# Steering_Wheel_Interface_Analog_Inputs.net
KiCad netlist of a schematic drawn in Altium Designer
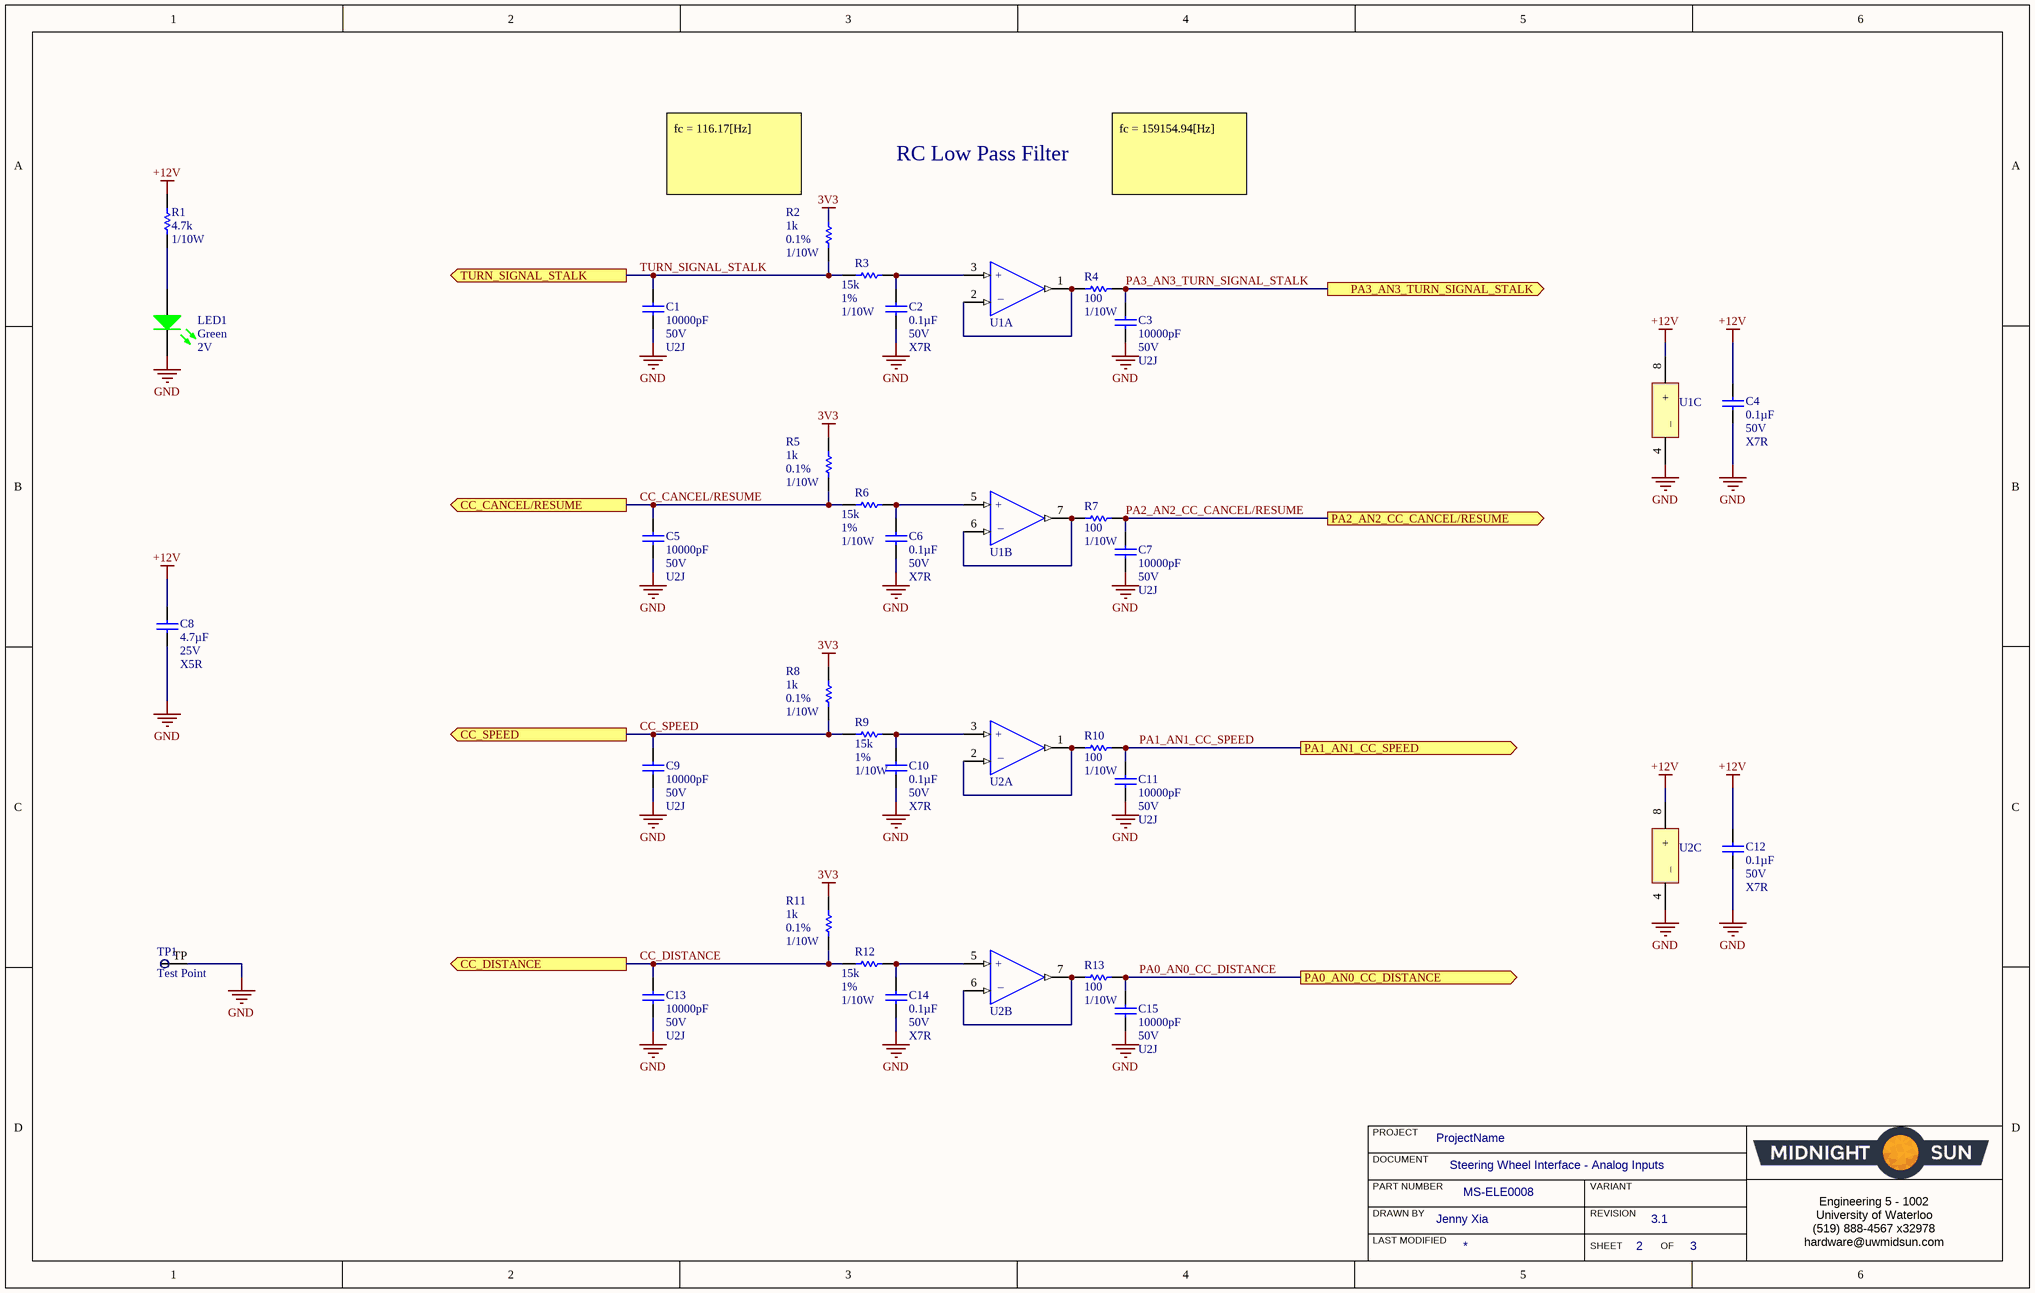
[diagram p0: Steering Wheel Interface Analog Inputs.SchDoc]

(export (version "E")
  (design (tool "Eeschema 10.0.6"))
  (components
    (comp (ref "C1")
      (value "CAP CER 10nF 50V 5% X7R 0603")
      (footprint "CAP, 0603")
      (description "10000pF ±5% 50V Ceramic Capacitor U2J 0603 (1608 Metric)")
      (fields
        (field (name "TOLERANCE") "±5%")
        (field (name "CAPACITANCE") "10000pF")
        (field (name "VOLTAGE") "50V")
        (field (name "TEMPERATURE COEFFICIENT") "U2J")
      )
      (libsource (lib "Schematic Diagrams") (part "CAP CER 10nF 50V 5% X7R 0603"))
    )
    (comp (ref "C2")
      (value "CAP CER 0.1UF 50V 10% X7R 0603")
      (footprint "CAP, 0603")
      (description "0.10µF ±10% 50V Ceramic Capacitor X7R 0603 (1608 Metric)")
      (fields
        (field (name "TOLERANCE") "±10%")
        (field (name "CAPACITANCE") "0.1µF")
        (field (name "VOLTAGE") "50V")
        (field (name "TEMPERATURE COEFFICIENT") "X7R")
      )
      (libsource (lib "Schematic Diagrams") (part "CAP CER 0.1UF 50V 10% X7R 0603"))
    )
    (comp (ref "C3")
      (value "CAP CER 10nF 50V 5% X7R 0603")
      (footprint "CAP, 0603")
      (description "10000pF ±5% 50V Ceramic Capacitor U2J 0603 (1608 Metric)")
      (fields
        (field (name "TOLERANCE") "±5%")
        (field (name "CAPACITANCE") "10000pF")
        (field (name "VOLTAGE") "50V")
        (field (name "TEMPERATURE COEFFICIENT") "U2J")
      )
      (libsource (lib "Schematic Diagrams") (part "CAP CER 10nF 50V 5% X7R 0603"))
    )
    (comp (ref "C4")
      (value "CAP CER 0.1UF 50V 10% X7R 0603")
      (footprint "CAP, 0603")
      (description "0.10µF ±10% 50V Ceramic Capacitor X7R 0603 (1608 Metric)")
      (fields
        (field (name "TOLERANCE") "±10%")
        (field (name "CAPACITANCE") "0.1µF")
        (field (name "VOLTAGE") "50V")
        (field (name "TEMPERATURE COEFFICIENT") "X7R")
      )
      (libsource (lib "Schematic Diagrams") (part "CAP CER 0.1UF 50V 10% X7R 0603"))
    )
    (comp (ref "C5")
      (value "CAP CER 10nF 50V 5% X7R 0603")
      (footprint "CAP, 0603")
      (description "10000pF ±5% 50V Ceramic Capacitor U2J 0603 (1608 Metric)")
      (fields
        (field (name "TOLERANCE") "±5%")
        (field (name "CAPACITANCE") "10000pF")
        (field (name "VOLTAGE") "50V")
        (field (name "TEMPERATURE COEFFICIENT") "U2J")
      )
      (libsource (lib "Schematic Diagrams") (part "CAP CER 10nF 50V 5% X7R 0603"))
    )
    (comp (ref "C6")
      (value "CAP CER 0.1UF 50V 10% X7R 0603")
      (footprint "CAP, 0603")
      (description "0.10µF ±10% 50V Ceramic Capacitor X7R 0603 (1608 Metric)")
      (fields
        (field (name "TOLERANCE") "±10%")
        (field (name "CAPACITANCE") "0.1µF")
        (field (name "VOLTAGE") "50V")
        (field (name "TEMPERATURE COEFFICIENT") "X7R")
      )
      (libsource (lib "Schematic Diagrams") (part "CAP CER 0.1UF 50V 10% X7R 0603"))
    )
    (comp (ref "C7")
      (value "CAP CER 10nF 50V 5% X7R 0603")
      (footprint "CAP, 0603")
      (description "10000pF ±5% 50V Ceramic Capacitor U2J 0603 (1608 Metric)")
      (fields
        (field (name "TOLERANCE") "±5%")
        (field (name "CAPACITANCE") "10000pF")
        (field (name "VOLTAGE") "50V")
        (field (name "TEMPERATURE COEFFICIENT") "U2J")
      )
      (libsource (lib "Schematic Diagrams") (part "CAP CER 10nF 50V 5% X7R 0603"))
    )
    (comp (ref "C8")
      (value "CAP CER 4.7UF 25V 10% X5R 0603")
      (footprint "CAP, 0603")
      (description "4.7µF ±10% 25V Ceramic Capacitor X5R 0603 (1608 Metric)")
      (fields
        (field (name "TOLERANCE") "±10%")
        (field (name "CAPACITANCE") "4.7µF")
        (field (name "VOLTAGE") "25V")
        (field (name "TEMPERATURE COEFFICIENT") "X5R")
      )
      (libsource (lib "Schematic Diagrams") (part "CAP CER 4.7UF 25V 10% X5R 0603"))
    )
    (comp (ref "C9")
      (value "CAP CER 10nF 50V 5% X7R 0603")
      (footprint "CAP, 0603")
      (description "10000pF ±5% 50V Ceramic Capacitor U2J 0603 (1608 Metric)")
      (fields
        (field (name "TOLERANCE") "±5%")
        (field (name "CAPACITANCE") "10000pF")
        (field (name "VOLTAGE") "50V")
        (field (name "TEMPERATURE COEFFICIENT") "U2J")
      )
      (libsource (lib "Schematic Diagrams") (part "CAP CER 10nF 50V 5% X7R 0603"))
    )
    (comp (ref "C10")
      (value "CAP CER 0.1UF 50V 10% X7R 0603")
      (footprint "CAP, 0603")
      (description "0.10µF ±10% 50V Ceramic Capacitor X7R 0603 (1608 Metric)")
      (fields
        (field (name "TOLERANCE") "±10%")
        (field (name "CAPACITANCE") "0.1µF")
        (field (name "VOLTAGE") "50V")
        (field (name "TEMPERATURE COEFFICIENT") "X7R")
      )
      (libsource (lib "Schematic Diagrams") (part "CAP CER 0.1UF 50V 10% X7R 0603"))
    )
    (comp (ref "C11")
      (value "CAP CER 10nF 50V 5% X7R 0603")
      (footprint "CAP, 0603")
      (description "10000pF ±5% 50V Ceramic Capacitor U2J 0603 (1608 Metric)")
      (fields
        (field (name "TOLERANCE") "±5%")
        (field (name "CAPACITANCE") "10000pF")
        (field (name "VOLTAGE") "50V")
        (field (name "TEMPERATURE COEFFICIENT") "U2J")
      )
      (libsource (lib "Schematic Diagrams") (part "CAP CER 10nF 50V 5% X7R 0603"))
    )
    (comp (ref "C12")
      (value "CAP CER 0.1UF 50V 10% X7R 0603")
      (footprint "CAP, 0603")
      (description "0.10µF ±10% 50V Ceramic Capacitor X7R 0603 (1608 Metric)")
      (fields
        (field (name "TOLERANCE") "±10%")
        (field (name "CAPACITANCE") "0.1µF")
        (field (name "VOLTAGE") "50V")
        (field (name "TEMPERATURE COEFFICIENT") "X7R")
      )
      (libsource (lib "Schematic Diagrams") (part "CAP CER 0.1UF 50V 10% X7R 0603"))
    )
    (comp (ref "C13")
      (value "CAP CER 10nF 50V 5% X7R 0603")
      (footprint "CAP, 0603")
      (description "10000pF ±5% 50V Ceramic Capacitor U2J 0603 (1608 Metric)")
      (fields
        (field (name "TOLERANCE") "±5%")
        (field (name "CAPACITANCE") "10000pF")
        (field (name "VOLTAGE") "50V")
        (field (name "TEMPERATURE COEFFICIENT") "U2J")
      )
      (libsource (lib "Schematic Diagrams") (part "CAP CER 10nF 50V 5% X7R 0603"))
    )
    (comp (ref "C14")
      (value "CAP CER 0.1UF 50V 10% X7R 0603")
      (footprint "CAP, 0603")
      (description "0.10µF ±10% 50V Ceramic Capacitor X7R 0603 (1608 Metric)")
      (fields
        (field (name "TOLERANCE") "±10%")
        (field (name "CAPACITANCE") "0.1µF")
        (field (name "VOLTAGE") "50V")
        (field (name "TEMPERATURE COEFFICIENT") "X7R")
      )
      (libsource (lib "Schematic Diagrams") (part "CAP CER 0.1UF 50V 10% X7R 0603"))
    )
    (comp (ref "C15")
      (value "CAP CER 10nF 50V 5% X7R 0603")
      (footprint "CAP, 0603")
      (description "10000pF ±5% 50V Ceramic Capacitor U2J 0603 (1608 Metric)")
      (fields
        (field (name "TOLERANCE") "±5%")
        (field (name "CAPACITANCE") "10000pF")
        (field (name "VOLTAGE") "50V")
        (field (name "TEMPERATURE COEFFICIENT") "U2J")
      )
      (libsource (lib "Schematic Diagrams") (part "CAP CER 10nF 50V 5% X7R 0603"))
    )
    (comp (ref "LED1")
      (value "LED GREEN CLEAR 2V 0603")
      (footprint "LED_0603")
      (description "Green 572nm LED Indication - Discrete 2V 0603 (1608 Metric)")
      (fields
        (field (name "MANUFACTURER") "Wurth Electronics Inc.")
        (field (name "MANUFACTURER PART NUMBER") "150060VS75000")
        (field (name "COLOR") "Green")
        (field (name "VOLTAGE - FORWARD (VF) (TYP)") "2V")
      )
      (libsource (lib "Schematic Diagrams") (part "LED GREEN CLEAR 2V 0603"))
    )
    (comp (ref "R1")
      (value "RES 4.7K OHM 1% 1/10W 0603")
      (footprint "RES, 0603")
      (description "4.7k Ohm ±1% 0.1W, 1/10W Chip Resistor 0603 (1608 Metric) Moisture Resistant Thick Film")
      (fields
        (field (name "TOLERANCE") "±1%")
        (field (name "RESISTANCE (OHMS)") "4.7k")
        (field (name "POWER (WATTS)") "1/10W")
      )
      (libsource (lib "Schematic Diagrams") (part "RES 4.7K OHM 1% 1/10W 0603"))
    )
    (comp (ref "R2")
      (value "RES SMD 1K OHM 0.1% 1/10W 0603")
      (footprint "RES, 0603")
      (description "1 kOhms ±0.1% 0.1W, 1/10W Chip Resistor 0603 (1608 Metric) Automotive AEC-Q200 Thin Film")
      (fields
        (field (name "MANUFACTURER") "Panasonic")
        (field (name "MANUFACTURER PART NUMBER") "ERA3AEB102V")
        (field (name "RESISTANCE") "1k")
        (field (name "TOLERANCE") "0.1%")
        (field (name "POWER RATING") "1/10W")
      )
      (libsource (lib "Schematic Diagrams") (part "RES SMD 1K OHM 0.1% 1/10W 0603"))
    )
    (comp (ref "R3")
      (value "RES SMD 15K OHM 1% 1/10W 0603")
      (footprint "RES, 0603")
      (description "15 kOhms ±1% 0.1W, 1/10W Chip Resistor 0603 (1608 Metric) Moisture Resistant Thick Film")
      (fields
        (field (name "RESISTANCE") "15k")
        (field (name "TOLERANCE") "1%")
        (field (name "MAX POWER DISSIPATION") "1/10W")
        (field (name "MANUFACTURER") "Yageo")
        (field (name "MANUFACTURER PART NUMBER") "RC0603FR-0715KL")
      )
      (libsource (lib "Schematic Diagrams") (part "RES SMD 15K OHM 1% 1/10W 0603"))
    )
    (comp (ref "R4")
      (value "RES 100 OHM 1% 1/10W 0603")
      (footprint "RES, 0603")
      (description "100 Ohm ±1% 0.1W, 1/10W Chip Resistor 0603 (1608 Metric) Moisture Resistant Thick Film")
      (fields
        (field (name "TOLERANCE") "±1%")
        (field (name "RESISTANCE") "100")
        (field (name "POWER") "1/10W")
      )
      (libsource (lib "Schematic Diagrams") (part "RES 100 OHM 1% 1/10W 0603"))
    )
    (comp (ref "R5")
      (value "RES SMD 1K OHM 0.1% 1/10W 0603")
      (footprint "RES, 0603")
      (description "1 kOhms ±0.1% 0.1W, 1/10W Chip Resistor 0603 (1608 Metric) Automotive AEC-Q200 Thin Film")
      (fields
        (field (name "MANUFACTURER") "Panasonic")
        (field (name "MANUFACTURER PART NUMBER") "ERA3AEB102V")
        (field (name "RESISTANCE") "1k")
        (field (name "TOLERANCE") "0.1%")
        (field (name "POWER RATING") "1/10W")
      )
      (libsource (lib "Schematic Diagrams") (part "RES SMD 1K OHM 0.1% 1/10W 0603"))
    )
    (comp (ref "R6")
      (value "RES SMD 15K OHM 1% 1/10W 0603")
      (footprint "RES, 0603")
      (description "15 kOhms ±1% 0.1W, 1/10W Chip Resistor 0603 (1608 Metric) Moisture Resistant Thick Film")
      (fields
        (field (name "RESISTANCE") "15k")
        (field (name "TOLERANCE") "1%")
        (field (name "MAX POWER DISSIPATION") "1/10W")
        (field (name "MANUFACTURER") "Yageo")
        (field (name "MANUFACTURER PART NUMBER") "RC0603FR-0715KL")
      )
      (libsource (lib "Schematic Diagrams") (part "RES SMD 15K OHM 1% 1/10W 0603"))
    )
    (comp (ref "R7")
      (value "RES 100 OHM 1% 1/10W 0603")
      (footprint "RES, 0603")
      (description "100 Ohm ±1% 0.1W, 1/10W Chip Resistor 0603 (1608 Metric) Moisture Resistant Thick Film")
      (fields
        (field (name "TOLERANCE") "±1%")
        (field (name "RESISTANCE") "100")
        (field (name "POWER") "1/10W")
      )
      (libsource (lib "Schematic Diagrams") (part "RES 100 OHM 1% 1/10W 0603"))
    )
    (comp (ref "R8")
      (value "RES SMD 1K OHM 0.1% 1/10W 0603")
      (footprint "RES, 0603")
      (description "1 kOhms ±0.1% 0.1W, 1/10W Chip Resistor 0603 (1608 Metric) Automotive AEC-Q200 Thin Film")
      (fields
        (field (name "MANUFACTURER") "Panasonic")
        (field (name "MANUFACTURER PART NUMBER") "ERA3AEB102V")
        (field (name "RESISTANCE") "1k")
        (field (name "TOLERANCE") "0.1%")
        (field (name "POWER RATING") "1/10W")
      )
      (libsource (lib "Schematic Diagrams") (part "RES SMD 1K OHM 0.1% 1/10W 0603"))
    )
    (comp (ref "R9")
      (value "RES SMD 15K OHM 1% 1/10W 0603")
      (footprint "RES, 0603")
      (description "15 kOhms ±1% 0.1W, 1/10W Chip Resistor 0603 (1608 Metric) Moisture Resistant Thick Film")
      (fields
        (field (name "RESISTANCE") "15k")
        (field (name "TOLERANCE") "1%")
        (field (name "MAX POWER DISSIPATION") "1/10W")
        (field (name "MANUFACTURER") "Yageo")
        (field (name "MANUFACTURER PART NUMBER") "RC0603FR-0715KL")
      )
      (libsource (lib "Schematic Diagrams") (part "RES SMD 15K OHM 1% 1/10W 0603"))
    )
    (comp (ref "R10")
      (value "RES 100 OHM 1% 1/10W 0603")
      (footprint "RES, 0603")
      (description "100 Ohm ±1% 0.1W, 1/10W Chip Resistor 0603 (1608 Metric) Moisture Resistant Thick Film")
      (fields
        (field (name "TOLERANCE") "±1%")
        (field (name "RESISTANCE") "100")
        (field (name "POWER") "1/10W")
      )
      (libsource (lib "Schematic Diagrams") (part "RES 100 OHM 1% 1/10W 0603"))
    )
    (comp (ref "R11")
      (value "RES SMD 1K OHM 0.1% 1/10W 0603")
      (footprint "RES, 0603")
      (description "1 kOhms ±0.1% 0.1W, 1/10W Chip Resistor 0603 (1608 Metric) Automotive AEC-Q200 Thin Film")
      (fields
        (field (name "RESISTANCE") "1k")
        (field (name "TOLERANCE") "0.1%")
        (field (name "POWER RATING") "1/10W")
        (field (name "MANUFACTURER") "Panasonic")
        (field (name "MANUFACTURER PART NUMBER") "ERA3AEB102V")
      )
      (libsource (lib "Schematic Diagrams") (part "RES SMD 1K OHM 0.1% 1/10W 0603"))
    )
    (comp (ref "R12")
      (value "RES SMD 15K OHM 1% 1/10W 0603")
      (footprint "RES, 0603")
      (description "15 kOhms ±1% 0.1W, 1/10W Chip Resistor 0603 (1608 Metric) Moisture Resistant Thick Film")
      (fields
        (field (name "RESISTANCE") "15k")
        (field (name "TOLERANCE") "1%")
        (field (name "MAX POWER DISSIPATION") "1/10W")
        (field (name "MANUFACTURER") "Yageo")
        (field (name "MANUFACTURER PART NUMBER") "RC0603FR-0715KL")
      )
      (libsource (lib "Schematic Diagrams") (part "RES SMD 15K OHM 1% 1/10W 0603"))
    )
    (comp (ref "R13")
      (value "RES 100 OHM 1% 1/10W 0603")
      (footprint "RES, 0603")
      (description "100 Ohm ±1% 0.1W, 1/10W Chip Resistor 0603 (1608 Metric) Moisture Resistant Thick Film")
      (fields
        (field (name "TOLERANCE") "±1%")
        (field (name "RESISTANCE") "100")
        (field (name "POWER") "1/10W")
      )
      (libsource (lib "Schematic Diagrams") (part "RES 100 OHM 1% 1/10W 0603"))
    )
    (comp (ref "TP1")
      (value "Test Point")
      (footprint "Test Point")
      (libsource (lib "Schematic Diagrams") (part "Test Point"))
    )
    (comp (ref "U1")
      (value "IC OP AMP DUAL GP RR 10MHZ 8-VSSOP")
      (footprint "IC OP AMP DUAL 8-VSSOP")
      (description "General Purpose Amplifier 2 Circuit Rail-to-Rail 8-VSSOP")
      (fields
        (field (name "MANUFACTURER") "Texas Instruments")
        (field (name "MANUFACTURER PART NUMBER") "OPA2197IDGKR")
      )
      (libsource (lib "Schematic Diagrams") (part "IC OP AMP DUAL GP RR 10MHZ 8-VSSOP"))
    )
    (comp (ref "U2")
      (value "IC OP AMP DUAL GP RR 10MHZ 8-VSSOP")
      (footprint "IC OP AMP DUAL 8-VSSOP")
      (description "General Purpose Amplifier 2 Circuit Rail-to-Rail 8-VSSOP")
      (fields
        (field (name "MANUFACTURER") "Texas Instruments")
        (field (name "MANUFACTURER PART NUMBER") "OPA2197IDGKR")
      )
      (libsource (lib "Schematic Diagrams") (part "IC OP AMP DUAL GP RR 10MHZ 8-VSSOP"))
    )
  )
  (nets
    (net (code "1") (name "+12V") (class "Default")
      (node (ref "C12") (pin "1") (pinfunction "1_1") (pintype "passive"))
      (node (ref "C4") (pin "1") (pinfunction "1_1") (pintype "passive"))
      (node (ref "C8") (pin "1") (pinfunction "1_1") (pintype "passive"))
      (node (ref "R1") (pin "1") (pinfunction "1_1") (pintype "passive"))
      (node (ref "U1") (pin "8") (pinfunction "+_8") (pintype "power_in"))
      (node (ref "U2") (pin "8") (pinfunction "+_8") (pintype "power_in"))
    )
    (net (code "2") (name "/CC_CANCEL{slash}RESUME") (class "Default")
      (node (ref "C5") (pin "1") (pinfunction "1_1") (pintype "passive"))
      (node (ref "R5") (pin "2") (pinfunction "2_2") (pintype "passive"))
      (node (ref "R6") (pin "2") (pinfunction "2_2") (pintype "passive"))
    )
    (net (code "3") (name "/CC_DISTANCE") (class "Default")
      (node (ref "C13") (pin "1") (pinfunction "1_1") (pintype "passive"))
      (node (ref "R11") (pin "2") (pinfunction "2_2") (pintype "passive"))
      (node (ref "R12") (pin "2") (pinfunction "2_2") (pintype "passive"))
    )
    (net (code "4") (name "/CC_SPEED") (class "Default")
      (node (ref "C9") (pin "1") (pinfunction "1_1") (pintype "passive"))
      (node (ref "R8") (pin "2") (pinfunction "2_2") (pintype "passive"))
      (node (ref "R9") (pin "2") (pinfunction "2_2") (pintype "passive"))
    )
    (net (code "5") (name "/PA0_AN0_CC_DISTANCE") (class "Default")
      (node (ref "C15") (pin "1") (pinfunction "1_1") (pintype "passive"))
      (node (ref "R13") (pin "1") (pinfunction "1_1") (pintype "passive"))
    )
    (net (code "6") (name "/PA1_AN1_CC_SPEED") (class "Default")
      (node (ref "C11") (pin "1") (pinfunction "1_1") (pintype "passive"))
      (node (ref "R10") (pin "1") (pinfunction "1_1") (pintype "passive"))
    )
    (net (code "7") (name "/PA2_AN2_CC_CANCEL{slash}RESUME") (class "Default")
      (node (ref "C7") (pin "1") (pinfunction "1_1") (pintype "passive"))
      (node (ref "R7") (pin "1") (pinfunction "1_1") (pintype "passive"))
    )
    (net (code "8") (name "/PA3_AN3_TURN_SIGNAL_STALK") (class "Default")
      (node (ref "C3") (pin "1") (pinfunction "1_1") (pintype "passive"))
      (node (ref "R4") (pin "1") (pinfunction "1_1") (pintype "passive"))
    )
    (net (code "9") (name "/TURN_SIGNAL_STALK") (class "Default")
      (node (ref "C1") (pin "1") (pinfunction "1_1") (pintype "passive"))
      (node (ref "R2") (pin "2") (pinfunction "2_2") (pintype "passive"))
      (node (ref "R3") (pin "2") (pinfunction "2_2") (pintype "passive"))
    )
    (net (code "10") (name "3V3") (class "Default")
      (node (ref "R11") (pin "1") (pinfunction "1_1") (pintype "passive"))
      (node (ref "R2") (pin "1") (pinfunction "1_1") (pintype "passive"))
      (node (ref "R5") (pin "1") (pinfunction "1_1") (pintype "passive"))
      (node (ref "R8") (pin "1") (pinfunction "1_1") (pintype "passive"))
    )
    (net (code "11") (name "GND") (class "Default")
      (node (ref "C1") (pin "2") (pinfunction "2_2") (pintype "passive"))
      (node (ref "C10") (pin "2") (pinfunction "2_2") (pintype "passive"))
      (node (ref "C11") (pin "2") (pinfunction "2_2") (pintype "passive"))
      (node (ref "C12") (pin "2") (pinfunction "2_2") (pintype "passive"))
      (node (ref "C13") (pin "2") (pinfunction "2_2") (pintype "passive"))
      (node (ref "C14") (pin "2") (pinfunction "2_2") (pintype "passive"))
      (node (ref "C15") (pin "2") (pinfunction "2_2") (pintype "passive"))
      (node (ref "C2") (pin "2") (pinfunction "2_2") (pintype "passive"))
      (node (ref "C3") (pin "2") (pinfunction "2_2") (pintype "passive"))
      (node (ref "C4") (pin "2") (pinfunction "2_2") (pintype "passive"))
      (node (ref "C5") (pin "2") (pinfunction "2_2") (pintype "passive"))
      (node (ref "C6") (pin "2") (pinfunction "2_2") (pintype "passive"))
      (node (ref "C7") (pin "2") (pinfunction "2_2") (pintype "passive"))
      (node (ref "C8") (pin "2") (pinfunction "2_2") (pintype "passive"))
      (node (ref "C9") (pin "2") (pinfunction "2_2") (pintype "passive"))
      (node (ref "LED1") (pin "2") (pinfunction "K_2") (pintype "passive"))
      (node (ref "TP1") (pin "TP") (pinfunction "1_TP") (pintype "passive"))
      (node (ref "U1") (pin "4") (pinfunction "__4") (pintype "power_in"))
      (node (ref "U2") (pin "4") (pinfunction "__4") (pintype "power_in"))
    )
    (net (code "12") (name "Net-(LED1-A)") (class "Default")
      (node (ref "LED1") (pin "1") (pinfunction "A_1") (pintype "passive"))
      (node (ref "R1") (pin "2") (pinfunction "2_2") (pintype "passive"))
    )
    (net (code "13") (name "Net-(U1A-+IN_A)") (class "Default")
      (node (ref "C2") (pin "1") (pinfunction "1_1") (pintype "passive"))
      (node (ref "R3") (pin "1") (pinfunction "1_1") (pintype "passive"))
      (node (ref "U1") (pin "3") (pinfunction "+IN_A_3") (pintype "input"))
    )
    (net (code "14") (name "Net-(U1A--IN_A)") (class "Default")
      (node (ref "R4") (pin "2") (pinfunction "2_2") (pintype "passive"))
      (node (ref "U1") (pin "1") (pinfunction "OUT_A_1") (pintype "output"))
      (node (ref "U1") (pin "2") (pinfunction "-IN_A_2") (pintype "input"))
    )
    (net (code "15") (name "Net-(U1B-+IN_B)") (class "Default")
      (node (ref "C6") (pin "1") (pinfunction "1_1") (pintype "passive"))
      (node (ref "R6") (pin "1") (pinfunction "1_1") (pintype "passive"))
      (node (ref "U1") (pin "5") (pinfunction "+IN_B_5") (pintype "input"))
    )
    (net (code "16") (name "Net-(U1B--IN_B)") (class "Default")
      (node (ref "R7") (pin "2") (pinfunction "2_2") (pintype "passive"))
      (node (ref "U1") (pin "6") (pinfunction "-IN_B_6") (pintype "input"))
      (node (ref "U1") (pin "7") (pinfunction "OUT_B_7") (pintype "output"))
    )
    (net (code "17") (name "Net-(U2A-+IN_A)") (class "Default")
      (node (ref "C10") (pin "1") (pinfunction "1_1") (pintype "passive"))
      (node (ref "R9") (pin "1") (pinfunction "1_1") (pintype "passive"))
      (node (ref "U2") (pin "3") (pinfunction "+IN_A_3") (pintype "input"))
    )
    (net (code "18") (name "Net-(U2A--IN_A)") (class "Default")
      (node (ref "R10") (pin "2") (pinfunction "2_2") (pintype "passive"))
      (node (ref "U2") (pin "1") (pinfunction "OUT_A_1") (pintype "output"))
      (node (ref "U2") (pin "2") (pinfunction "-IN_A_2") (pintype "input"))
    )
    (net (code "19") (name "Net-(U2B-+IN_B)") (class "Default")
      (node (ref "C14") (pin "1") (pinfunction "1_1") (pintype "passive"))
      (node (ref "R12") (pin "1") (pinfunction "1_1") (pintype "passive"))
      (node (ref "U2") (pin "5") (pinfunction "+IN_B_5") (pintype "input"))
    )
    (net (code "20") (name "Net-(U2B--IN_B)") (class "Default")
      (node (ref "R13") (pin "2") (pinfunction "2_2") (pintype "passive"))
      (node (ref "U2") (pin "6") (pinfunction "-IN_B_6") (pintype "input"))
      (node (ref "U2") (pin "7") (pinfunction "OUT_B_7") (pintype "output"))
    )
  )
)
